# Vent_Schematic.net
KiCad netlist of a schematic drawn in EAGLE
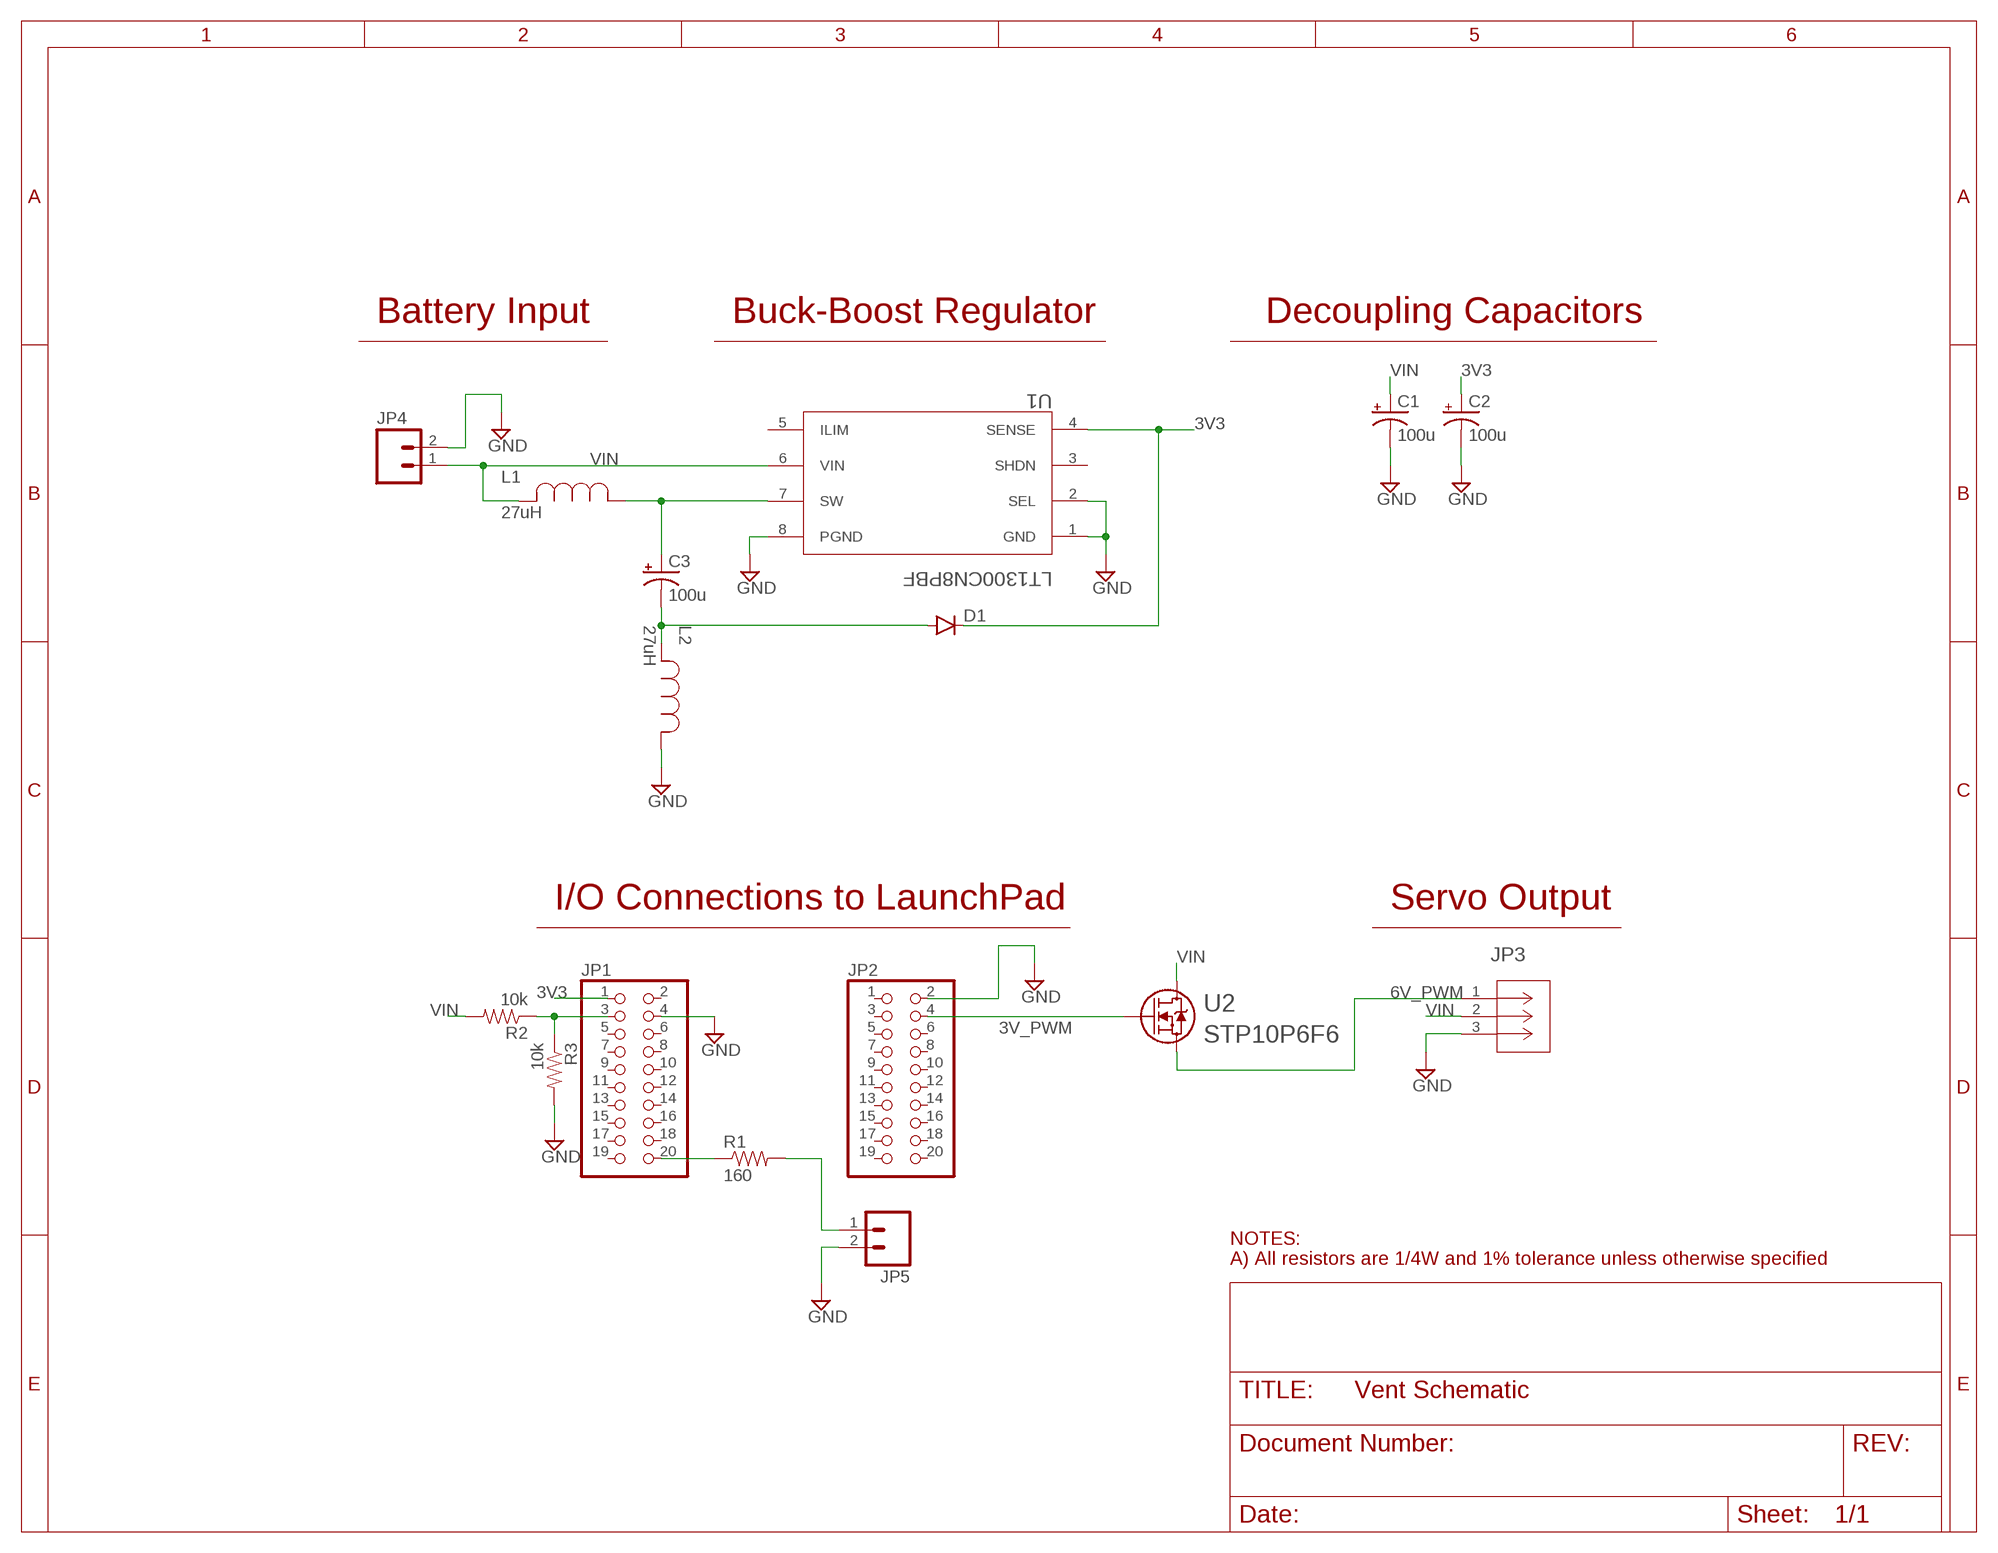
[diagram p0: schematic, sheet 1]

(export (version "E")
  (design (tool "Eeschema 10.0.6"))
  (components
    (comp (ref "C1")
      (value "100u")
      (footprint "eagle-import:CPOL-RADIAL-1000UF-25V")
      (libsource (lib "eagle-import") (part "1000UF-25V(PTH)"))
    )
    (comp (ref "C2")
      (value "100u")
      (footprint "eagle-import:CPOL-RADIAL-1000UF-25V")
      (libsource (lib "eagle-import") (part "1000UF-25V(PTH)"))
    )
    (comp (ref "C3")
      (value "100u")
      (footprint "eagle-import:CPOL-RADIAL-1000UF-25V")
      (libsource (lib "eagle-import") (part "1000UF-25V(PTH)"))
    )
    (comp (ref "D1")
      (value "DIODE1N4148")
      (footprint "eagle-import:DIODE-1N4148")
      (libsource (lib "eagle-import") (part "DIODE1N4148"))
    )
    (comp (ref "JP1")
      (value "PINHD-2X10")
      (footprint "eagle-import:2X10")
      (libsource (lib "eagle-import") (part "PINHD-2X10"))
    )
    (comp (ref "JP2")
      (value "PINHD-2X10")
      (footprint "eagle-import:2X10")
      (libsource (lib "eagle-import") (part "PINHD-2X10"))
    )
    (comp (ref "JP3")
      (value "DF3A-3P-2DS")
      (footprint "eagle-import:CON3_1X3_R_DF3")
      (fields (field (name "MANUFACTURER_PART_NUMBER") "DF3A3P2DS"))
      (libsource (lib "eagle-import") (part "DF3A-3P-2DS"))
    )
    (comp (ref "JP4")
      (value "M023.5MM")
      (footprint "eagle-import:SCREWTERMINAL-3.5MM-2")
      (libsource (lib "eagle-import") (part "M023.5MM"))
    )
    (comp (ref "JP5")
      (value "M023.5MM")
      (footprint "eagle-import:SCREWTERMINAL-3.5MM-2")
      (libsource (lib "eagle-import") (part "M023.5MM"))
    )
    (comp (ref "L1")
      (value "27uH")
      (footprint "eagle-import:IND_2100LL_42_H")
      (fields (field (name "MANUFACTURER_PART_NUMBER") "2100LL270HRC"))
      (libsource (lib "eagle-import") (part "2100LL-270-H-RC"))
    )
    (comp (ref "L2")
      (value "27uH")
      (footprint "eagle-import:IND_2100LL_42_H")
      (fields (field (name "MANUFACTURER_PART_NUMBER") "2100LL270HRC"))
      (libsource (lib "eagle-import") (part "2100LL-270-H-RC"))
    )
    (comp (ref "R1")
      (value "160")
      (footprint "eagle-import:AXIAL-0.3")
      (libsource (lib "eagle-import") (part "RESISTORAXIAL-0.3"))
    )
    (comp (ref "R2")
      (value "10k")
      (footprint "eagle-import:AXIAL-0.3")
      (libsource (lib "eagle-import") (part "RESISTORAXIAL-0.3"))
    )
    (comp (ref "R3")
      (value "10k")
      (footprint "eagle-import:AXIAL-0.3")
      (libsource (lib "eagle-import") (part "RESISTORAXIAL-0.3"))
    )
    (comp (ref "U1")
      (value "LT1300CN8PBF")
      (footprint "eagle-import:PDIP-8_N")
      (fields (field (name "MANUFACTURER_PART_NUMBER") "LT1300CN8#PBF"))
      (libsource (lib "eagle-import") (part "LT1300CN8PBF"))
    )
    (comp (ref "U2")
      (value "STP10P6F6")
      (footprint "eagle-import:TO-220")
      (libsource (lib "eagle-import") (part "STP10P6F6"))
    )
  )
  (nets
    (net (code "1") (name "/3V3") (class "Default")
      (node (ref "C2") (pin "+") (pinfunction "+_+") (pintype "passive"))
      (node (ref "D1") (pin "C") (pinfunction "C_C") (pintype "passive"))
      (node (ref "JP1") (pin "1") (pinfunction "1_1") (pintype "passive"))
      (node (ref "U1") (pin "4") (pinfunction "SENSE_4") (pintype "passive"))
    )
    (net (code "2") (name "/3V_PWM") (class "Default")
      (node (ref "JP2") (pin "4") (pinfunction "4_4") (pintype "passive"))
      (node (ref "U2") (pin "1") (pinfunction "1_1") (pintype "passive"))
    )
    (net (code "3") (name "/6V_PWM") (class "Default")
      (node (ref "JP3") (pin "1") (pinfunction "1_1") (pintype "passive"))
      (node (ref "U2") (pin "3") (pinfunction "3_3") (pintype "passive"))
    )
    (net (code "4") (name "/VIN") (class "Default")
      (node (ref "C1") (pin "+") (pinfunction "+_+") (pintype "passive"))
      (node (ref "JP3") (pin "2") (pinfunction "2_2") (pintype "passive"))
      (node (ref "JP4") (pin "1") (pinfunction "1_1") (pintype "passive"))
      (node (ref "L1") (pin "2") (pinfunction "2_2") (pintype "passive"))
      (node (ref "R2") (pin "P$2") (pinfunction "2_P$2") (pintype "passive"))
      (node (ref "U1") (pin "6") (pinfunction "VIN_6") (pintype "passive"))
      (node (ref "U2") (pin "2") (pinfunction "2_2") (pintype "passive"))
    )
    (net (code "5") (name "GND") (class "Default")
      (node (ref "C1") (pin "-") (pinfunction "-_-") (pintype "passive"))
      (node (ref "C2") (pin "-") (pinfunction "-_-") (pintype "passive"))
      (node (ref "JP1") (pin "4") (pinfunction "4_4") (pintype "passive"))
      (node (ref "JP2") (pin "2") (pinfunction "2_2") (pintype "passive"))
      (node (ref "JP3") (pin "3") (pinfunction "3_3") (pintype "passive"))
      (node (ref "JP4") (pin "2") (pinfunction "2_2") (pintype "passive"))
      (node (ref "JP5") (pin "2") (pinfunction "2_2") (pintype "passive"))
      (node (ref "L2") (pin "1") (pinfunction "1_1") (pintype "passive"))
      (node (ref "R3") (pin "P$2") (pinfunction "2_P$2") (pintype "passive"))
      (node (ref "U1") (pin "1") (pinfunction "GND_1") (pintype "power_in"))
      (node (ref "U1") (pin "2") (pinfunction "SEL_2") (pintype "passive"))
      (node (ref "U1") (pin "8") (pinfunction "PGND_8") (pintype "power_in"))
    )
    (net (code "6") (name "Net-(C3-Pad-)") (class "Default")
      (node (ref "C3") (pin "-") (pinfunction "-_-") (pintype "passive"))
      (node (ref "D1") (pin "A") (pinfunction "A_A") (pintype "passive"))
      (node (ref "L2") (pin "2") (pinfunction "2_2") (pintype "passive"))
    )
    (net (code "7") (name "Net-(R1-1)") (class "Default")
      (node (ref "JP1") (pin "20") (pinfunction "20_20") (pintype "passive"))
      (node (ref "R1") (pin "P$1") (pinfunction "1_P$1") (pintype "passive"))
    )
    (net (code "8") (name "Net-(R1-2)") (class "Default")
      (node (ref "JP5") (pin "1") (pinfunction "1_1") (pintype "passive"))
      (node (ref "R1") (pin "P$2") (pinfunction "2_P$2") (pintype "passive"))
    )
    (net (code "9") (name "Net-(R2-1)") (class "Default")
      (node (ref "JP1") (pin "3") (pinfunction "3_3") (pintype "passive"))
      (node (ref "R2") (pin "P$1") (pinfunction "1_P$1") (pintype "passive"))
      (node (ref "R3") (pin "P$1") (pinfunction "1_P$1") (pintype "passive"))
    )
    (net (code "10") (name "Net-(U1-SW)") (class "Default")
      (node (ref "C3") (pin "+") (pinfunction "+_+") (pintype "passive"))
      (node (ref "L1") (pin "1") (pinfunction "1_1") (pintype "passive"))
      (node (ref "U1") (pin "7") (pinfunction "SW_7") (pintype "passive"))
    )
    (net (code "11") (name "unconnected-(JP1-Pad2)") (class "Default")
      (node (ref "JP1") (pin "2") (pinfunction "2_2") (pintype "passive"))
    )
    (net (code "12") (name "unconnected-(JP1-Pad5)") (class "Default")
      (node (ref "JP1") (pin "5") (pinfunction "5_5") (pintype "passive"))
    )
    (net (code "13") (name "unconnected-(JP1-Pad6)") (class "Default")
      (node (ref "JP1") (pin "6") (pinfunction "6_6") (pintype "passive"))
    )
    (net (code "14") (name "unconnected-(JP1-Pad7)") (class "Default")
      (node (ref "JP1") (pin "7") (pinfunction "7_7") (pintype "passive"))
    )
    (net (code "15") (name "unconnected-(JP1-Pad8)") (class "Default")
      (node (ref "JP1") (pin "8") (pinfunction "8_8") (pintype "passive"))
    )
    (net (code "16") (name "unconnected-(JP1-Pad9)") (class "Default")
      (node (ref "JP1") (pin "9") (pinfunction "9_9") (pintype "passive"))
    )
    (net (code "17") (name "unconnected-(JP1-Pad10)") (class "Default")
      (node (ref "JP1") (pin "10") (pinfunction "10_10") (pintype "passive"))
    )
    (net (code "18") (name "unconnected-(JP1-Pad11)") (class "Default")
      (node (ref "JP1") (pin "11") (pinfunction "11_11") (pintype "passive"))
    )
    (net (code "19") (name "unconnected-(JP1-Pad12)") (class "Default")
      (node (ref "JP1") (pin "12") (pinfunction "12_12") (pintype "passive"))
    )
    (net (code "20") (name "unconnected-(JP1-Pad13)") (class "Default")
      (node (ref "JP1") (pin "13") (pinfunction "13_13") (pintype "passive"))
    )
    (net (code "21") (name "unconnected-(JP1-Pad14)") (class "Default")
      (node (ref "JP1") (pin "14") (pinfunction "14_14") (pintype "passive"))
    )
    (net (code "22") (name "unconnected-(JP1-Pad15)") (class "Default")
      (node (ref "JP1") (pin "15") (pinfunction "15_15") (pintype "passive"))
    )
    (net (code "23") (name "unconnected-(JP1-Pad16)") (class "Default")
      (node (ref "JP1") (pin "16") (pinfunction "16_16") (pintype "passive"))
    )
    (net (code "24") (name "unconnected-(JP1-Pad17)") (class "Default")
      (node (ref "JP1") (pin "17") (pinfunction "17_17") (pintype "passive"))
    )
    (net (code "25") (name "unconnected-(JP1-Pad18)") (class "Default")
      (node (ref "JP1") (pin "18") (pinfunction "18_18") (pintype "passive"))
    )
    (net (code "26") (name "unconnected-(JP1-Pad19)") (class "Default")
      (node (ref "JP1") (pin "19") (pinfunction "19_19") (pintype "passive"))
    )
    (net (code "27") (name "unconnected-(JP2-Pad1)") (class "Default")
      (node (ref "JP2") (pin "1") (pinfunction "1_1") (pintype "passive"))
    )
    (net (code "28") (name "unconnected-(JP2-Pad3)") (class "Default")
      (node (ref "JP2") (pin "3") (pinfunction "3_3") (pintype "passive"))
    )
    (net (code "29") (name "unconnected-(JP2-Pad5)") (class "Default")
      (node (ref "JP2") (pin "5") (pinfunction "5_5") (pintype "passive"))
    )
    (net (code "30") (name "unconnected-(JP2-Pad6)") (class "Default")
      (node (ref "JP2") (pin "6") (pinfunction "6_6") (pintype "passive"))
    )
    (net (code "31") (name "unconnected-(JP2-Pad7)") (class "Default")
      (node (ref "JP2") (pin "7") (pinfunction "7_7") (pintype "passive"))
    )
    (net (code "32") (name "unconnected-(JP2-Pad8)") (class "Default")
      (node (ref "JP2") (pin "8") (pinfunction "8_8") (pintype "passive"))
    )
    (net (code "33") (name "unconnected-(JP2-Pad9)") (class "Default")
      (node (ref "JP2") (pin "9") (pinfunction "9_9") (pintype "passive"))
    )
    (net (code "34") (name "unconnected-(JP2-Pad10)") (class "Default")
      (node (ref "JP2") (pin "10") (pinfunction "10_10") (pintype "passive"))
    )
    (net (code "35") (name "unconnected-(JP2-Pad11)") (class "Default")
      (node (ref "JP2") (pin "11") (pinfunction "11_11") (pintype "passive"))
    )
    (net (code "36") (name "unconnected-(JP2-Pad12)") (class "Default")
      (node (ref "JP2") (pin "12") (pinfunction "12_12") (pintype "passive"))
    )
    (net (code "37") (name "unconnected-(JP2-Pad13)") (class "Default")
      (node (ref "JP2") (pin "13") (pinfunction "13_13") (pintype "passive"))
    )
    (net (code "38") (name "unconnected-(JP2-Pad14)") (class "Default")
      (node (ref "JP2") (pin "14") (pinfunction "14_14") (pintype "passive"))
    )
    (net (code "39") (name "unconnected-(JP2-Pad15)") (class "Default")
      (node (ref "JP2") (pin "15") (pinfunction "15_15") (pintype "passive"))
    )
    (net (code "40") (name "unconnected-(JP2-Pad16)") (class "Default")
      (node (ref "JP2") (pin "16") (pinfunction "16_16") (pintype "passive"))
    )
    (net (code "41") (name "unconnected-(JP2-Pad17)") (class "Default")
      (node (ref "JP2") (pin "17") (pinfunction "17_17") (pintype "passive"))
    )
    (net (code "42") (name "unconnected-(JP2-Pad18)") (class "Default")
      (node (ref "JP2") (pin "18") (pinfunction "18_18") (pintype "passive"))
    )
    (net (code "43") (name "unconnected-(JP2-Pad19)") (class "Default")
      (node (ref "JP2") (pin "19") (pinfunction "19_19") (pintype "passive"))
    )
    (net (code "44") (name "unconnected-(JP2-Pad20)") (class "Default")
      (node (ref "JP2") (pin "20") (pinfunction "20_20") (pintype "passive"))
    )
    (net (code "45") (name "unconnected-(U1-ILIM-Pad5)") (class "Default")
      (node (ref "U1") (pin "5") (pinfunction "ILIM_5") (pintype "passive"))
    )
    (net (code "46") (name "unconnected-(U1-SHDN-Pad3)") (class "Default")
      (node (ref "U1") (pin "3") (pinfunction "SHDN_3") (pintype "passive"))
    )
  )
)
